# Discrete-Buck.net
KiCad netlist of a schematic drawn in EasyEDA Pro
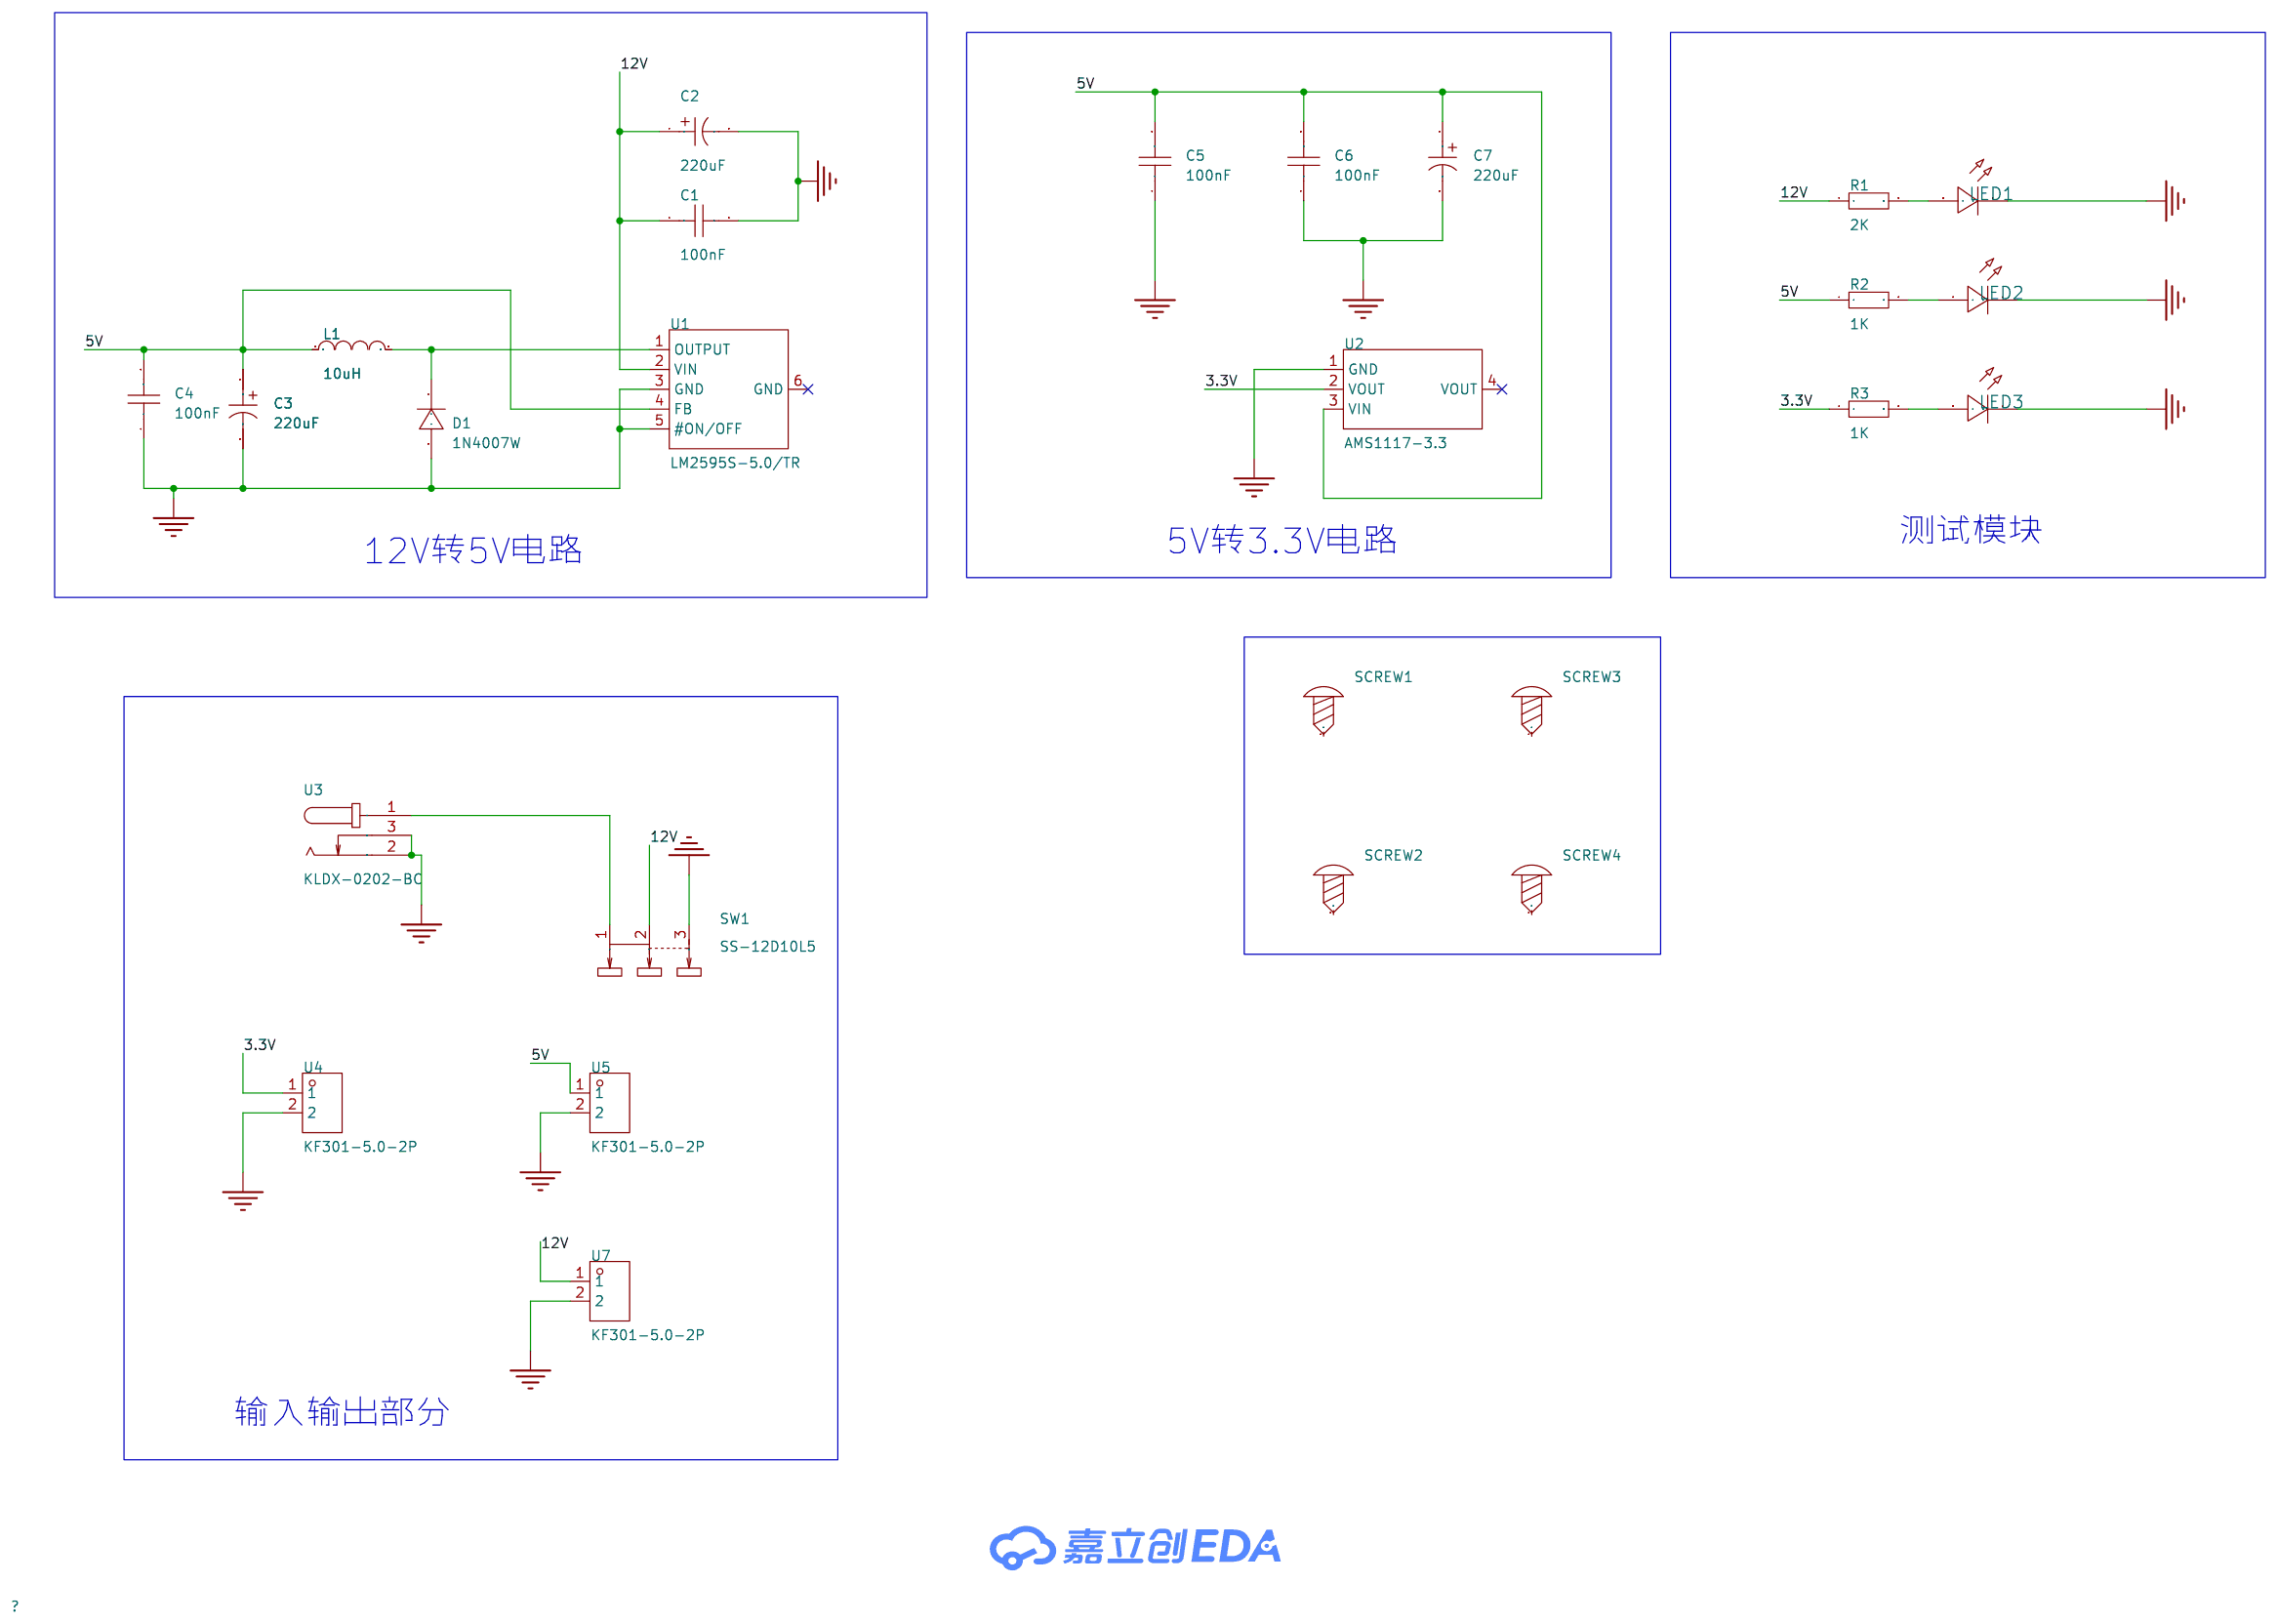
[diagram p0: schematic sheet]

(export (version "E")
  (design (tool "Eeschema 10.0.6"))
  (components
    (comp (ref "C1")
      (value "100nF")
      (footprint "easyedapro:C0603")
      (libsource (lib "easyedapro") (part "Capacitance"))
    )
    (comp (ref "C2")
      (value "220uF")
      (footprint "easyedapro:CAP-TH_BD6.3-P2.50-D0.5-FD")
      (description "容值:220uF;精度:±20%;额定电压:16V;纹波电流:300mA@100kHz;等效串联电阻(ESR):220mΩ@100kHz;")
      (fields (field (name "Manufacturer Part") "ERG16V220M6X7") (field (name "Manufacturer") "JIERR(捷而瑞)"))
      (libsource (lib "easyedapro") (part "ERG16V220M6X7"))
    )
    (comp (ref "C3")
      (value "220uF")
      (footprint "easyedapro:CAP-TH_BD6.3-P2.50-D0.5-FD")
      (description "容值:220uF;精度:±20%;额定电压:16V;纹波电流:300mA@100kHz;等效串联电阻(ESR):220mΩ@100kHz;")
      (fields (field (name "Manufacturer Part") "ERG16V220M6X7") (field (name "Manufacturer") "JIERR(捷而瑞)"))
      (libsource (lib "easyedapro") (part "ERG16V220M6X7"))
    )
    (comp (ref "C4")
      (value "100nF")
      (footprint "easyedapro:C0603")
      (libsource (lib "easyedapro") (part "Capacitance"))
    )
    (comp (ref "C5")
      (value "100nF")
      (footprint "easyedapro:C0603")
      (libsource (lib "easyedapro") (part "Capacitance"))
    )
    (comp (ref "C6")
      (value "100nF")
      (footprint "easyedapro:C0603")
      (libsource (lib "easyedapro") (part "Capacitance"))
    )
    (comp (ref "C7")
      (value "220uF")
      (footprint "easyedapro:CAP-TH_BD6.3-P2.50-D0.5-FD")
      (description "容值:220uF;精度:±20%;额定电压:16V;纹波电流:300mA@100kHz;等效串联电阻(ESR):220mΩ@100kHz;")
      (fields (field (name "Manufacturer Part") "ERG16V220M6X7") (field (name "Manufacturer") "JIERR(捷而瑞)"))
      (libsource (lib "easyedapro") (part "ERG16V220M6X7"))
    )
    (comp (ref "D1")
      (value "1N4007W")
      (footprint "easyedapro:SOD-123FL_L2.7-W1.8-LS3.8-RD")
      (description "二极管配置:独立式;正向压降(Vf):1V@1.0A;直流反向耐压(Vr):1kV;整流电流:1A;")
      (fields (field (name "Manufacturer") "R+O(宏嘉诚)"))
      (libsource (lib "easyedapro") (part "1N4007W_C18199088"))
    )
    (comp (ref "L1")
      (value "10uH")
      (footprint "easyedapro:L0603")
      (libsource (lib "easyedapro") (part "SDFL1608S100KTF"))
    )
    (comp (ref "LED1")
      (value "~")
      (footprint "easyedapro:LED_0603")
      (libsource (lib "easyedapro") (part "LED_R"))
    )
    (comp (ref "LED2")
      (value "~")
      (footprint "easyedapro:LED_0603")
      (libsource (lib "easyedapro") (part "LED_R"))
    )
    (comp (ref "LED3")
      (value "~")
      (footprint "easyedapro:LED_0603")
      (libsource (lib "easyedapro") (part "LED_R"))
    )
    (comp (ref "R1") (value "2K") (footprint "easyedapro:R0603") (libsource (lib "easyedapro") (part "电阻")))
    (comp (ref "R2") (value "1K") (footprint "easyedapro:R0603") (libsource (lib "easyedapro") (part "电阻")))
    (comp (ref "R3") (value "1K") (footprint "easyedapro:R0603") (libsource (lib "easyedapro") (part "电阻")))
    (comp (ref "SCREW1")
      (value "~")
      (footprint "easyedapro:M2螺丝")
      (libsource (lib "easyedapro") (part "螺丝孔"))
    )
    (comp (ref "SCREW2")
      (value "~")
      (footprint "easyedapro:M2螺丝")
      (libsource (lib "easyedapro") (part "螺丝孔"))
    )
    (comp (ref "SCREW3")
      (value "~")
      (footprint "easyedapro:M2螺丝")
      (libsource (lib "easyedapro") (part "螺丝孔"))
    )
    (comp (ref "SCREW4")
      (value "~")
      (footprint "easyedapro:M2螺丝")
      (libsource (lib "easyedapro") (part "螺丝孔"))
    )
    (comp (ref "SW1")
      (value "SS-12D10L5")
      (footprint "easyedapro:SW-TH_SS-12D10L5")
      (description "电路结构:单刀双掷;安装方式:直插;开关颜色:黑色;额定电流:3A;额定电压:125V;工作寿命:1万次;")
      (fields (field (name "Manufacturer") "XKB Connection(中国星坤)"))
      (libsource (lib "easyedapro") (part "SS-12D10L5"))
    )
    (comp (ref "U1")
      (value "LM2595S-5.0/TR")
      (footprint "easyedapro:TO-263-5_L10.6-W9.6-P1.70-LS15.9-BR")
      (description "功能类型:降压型;输出类型:固定;工作电压:4.5V~40V;输出电压:5V;输出电流:3A;")
      (fields (field (name "Manufacturer") "HGSEMI(华冠)"))
      (libsource (lib "easyedapro") (part "LM2595S-5.0/TR"))
    )
    (comp (ref "U2")
      (value "AMS1117-3.3")
      (footprint "easyedapro:SOT-223-3_L6.5-W3.4-P2.30-LS7.0-BR")
      (description "输出类型:固定;工作电压:16V;输出电压:3.3V;输出电流:1A;电源纹波抑制比(PSRR):72dB@(120Hz);输出极性:正极;")
      (fields (field (name "Manufacturer") "AMS"))
      (libsource (lib "easyedapro") (part "AMS1117-3.3"))
    )
    (comp (ref "U3")
      (value "KLDX-0202-BC")
      (footprint "easyedapro:DC-IN-TH_KH-DC-005-2.5")
      (fields (field (name "Manufacturer") "Kycon"))
      (libsource (lib "easyedapro") (part "KLDX-0202-BC"))
    )
    (comp (ref "U4")
      (value "KF301-5.0-2P")
      (footprint "easyedapro:CONN-TH_P5.00_KF301-5.0-2P")
      (fields (field (name "Manufacturer") "KEFA(科发)"))
      (libsource (lib "easyedapro") (part "KF301-5.0-2P"))
    )
    (comp (ref "U5")
      (value "KF301-5.0-2P")
      (footprint "easyedapro:CONN-TH_P5.00_KF301-5.0-2P")
      (fields (field (name "Manufacturer") "KEFA(科发)"))
      (libsource (lib "easyedapro") (part "KF301-5.0-2P"))
    )
    (comp (ref "U7")
      (value "KF301-5.0-2P")
      (footprint "easyedapro:CONN-TH_P5.00_KF301-5.0-2P")
      (fields (field (name "Manufacturer") "KEFA(科发)"))
      (libsource (lib "easyedapro") (part "KF301-5.0-2P"))
    )
  )
  (nets
    (net (code "1") (name "/3.3V") (class "Default")
      (node (ref "R3") (pin "1") (pinfunction "1_1") (pintype "input"))
      (node (ref "U2") (pin "2") (pinfunction "VOUT_2") (pintype "unspecified"))
      (node (ref "U4") (pin "1") (pinfunction "1_1") (pintype "unspecified"))
    )
    (net (code "2") (name "/5V") (class "Default")
      (node (ref "C3") (pin "1") (pinfunction "1_1") (pintype "input"))
      (node (ref "C4") (pin "2") (pinfunction "2_2") (pintype "input"))
      (node (ref "C5") (pin "2") (pinfunction "2_2") (pintype "input"))
      (node (ref "C6") (pin "2") (pinfunction "2_2") (pintype "input"))
      (node (ref "C7") (pin "1") (pinfunction "1_1") (pintype "input"))
      (node (ref "L1") (pin "1") (pinfunction "1_1") (pintype "unspecified"))
      (node (ref "R2") (pin "1") (pinfunction "1_1") (pintype "input"))
      (node (ref "U1") (pin "4") (pinfunction "FB_4") (pintype "unspecified"))
      (node (ref "U2") (pin "3") (pinfunction "VIN_3") (pintype "unspecified"))
      (node (ref "U5") (pin "1") (pinfunction "1_1") (pintype "unspecified"))
    )
    (net (code "3") (name "/12V") (class "Default")
      (node (ref "C1") (pin "1") (pinfunction "1_1") (pintype "input"))
      (node (ref "C2") (pin "1") (pinfunction "1_1") (pintype "input"))
      (node (ref "R1") (pin "1") (pinfunction "1_1") (pintype "input"))
      (node (ref "SW1") (pin "2") (pinfunction "2_2") (pintype "unspecified"))
      (node (ref "U1") (pin "2") (pinfunction "VIN_2") (pintype "unspecified"))
      (node (ref "U7") (pin "1") (pinfunction "1_1") (pintype "unspecified"))
    )
    (net (code "4") (name "GND") (class "Default")
      (node (ref "C1") (pin "2") (pinfunction "2_2") (pintype "input"))
      (node (ref "C2") (pin "2") (pinfunction "2_2") (pintype "input"))
      (node (ref "C3") (pin "2") (pinfunction "2_2") (pintype "input"))
      (node (ref "C4") (pin "1") (pinfunction "1_1") (pintype "input"))
      (node (ref "C5") (pin "1") (pinfunction "1_1") (pintype "input"))
      (node (ref "C6") (pin "1") (pinfunction "1_1") (pintype "input"))
      (node (ref "C7") (pin "2") (pinfunction "2_2") (pintype "input"))
      (node (ref "D1") (pin "2") (pinfunction "A_2") (pintype "unspecified"))
      (node (ref "LED1") (pin "1") (pinfunction "C_1") (pintype "input"))
      (node (ref "LED2") (pin "1") (pinfunction "C_1") (pintype "input"))
      (node (ref "LED3") (pin "1") (pinfunction "C_1") (pintype "input"))
      (node (ref "SW1") (pin "3") (pinfunction "3_3") (pintype "unspecified"))
      (node (ref "U1") (pin "3") (pinfunction "GND_3") (pintype "unspecified"))
      (node (ref "U1") (pin "5") (pinfunction "#ON/OFF_5") (pintype "unspecified"))
      (node (ref "U2") (pin "1") (pinfunction "GND_1") (pintype "unspecified"))
      (node (ref "U3") (pin "2") (pinfunction "2_2") (pintype "unspecified"))
      (node (ref "U3") (pin "3") (pinfunction "3_3") (pintype "unspecified"))
      (node (ref "U4") (pin "2") (pinfunction "2_2") (pintype "unspecified"))
      (node (ref "U5") (pin "2") (pinfunction "2_2") (pintype "unspecified"))
      (node (ref "U7") (pin "2") (pinfunction "2_2") (pintype "unspecified"))
    )
    (net (code "5") (name "Net-(D1-K)") (class "Default")
      (node (ref "D1") (pin "1") (pinfunction "K_1") (pintype "unspecified"))
      (node (ref "L1") (pin "2") (pinfunction "2_2") (pintype "unspecified"))
      (node (ref "U1") (pin "1") (pinfunction "OUTPUT_1") (pintype "unspecified"))
    )
    (net (code "6") (name "Net-(LED1-A)") (class "Default")
      (node (ref "LED1") (pin "2") (pinfunction "A_2") (pintype "input"))
      (node (ref "R1") (pin "2") (pinfunction "2_2") (pintype "input"))
    )
    (net (code "7") (name "Net-(LED2-A)") (class "Default")
      (node (ref "LED2") (pin "2") (pinfunction "A_2") (pintype "input"))
      (node (ref "R2") (pin "2") (pinfunction "2_2") (pintype "input"))
    )
    (net (code "8") (name "Net-(LED3-A)") (class "Default")
      (node (ref "LED3") (pin "2") (pinfunction "A_2") (pintype "input"))
      (node (ref "R3") (pin "2") (pinfunction "2_2") (pintype "input"))
    )
    (net (code "9") (name "Net-(SW1-Pad1)") (class "Default")
      (node (ref "SW1") (pin "1") (pinfunction "1_1") (pintype "unspecified"))
      (node (ref "U3") (pin "1") (pinfunction "1_1") (pintype "unspecified"))
    )
    (net (code "10") (name "unconnected-(SCREW1-Pad1)") (class "Default")
      (node (ref "SCREW1") (pin "1") (pinfunction "1_1") (pintype "input"))
    )
    (net (code "11") (name "unconnected-(SCREW2-Pad1)") (class "Default")
      (node (ref "SCREW2") (pin "1") (pinfunction "1_1") (pintype "input"))
    )
    (net (code "12") (name "unconnected-(SCREW3-Pad1)") (class "Default")
      (node (ref "SCREW3") (pin "1") (pinfunction "1_1") (pintype "input"))
    )
    (net (code "13") (name "unconnected-(SCREW4-Pad1)") (class "Default")
      (node (ref "SCREW4") (pin "1") (pinfunction "1_1") (pintype "input"))
    )
    (net (code "14") (name "unconnected-(U1-GND-Pad6)") (class "Default")
      (node (ref "U1") (pin "6") (pinfunction "GND_6") (pintype "unspecified+no_connect"))
    )
    (net (code "15") (name "unconnected-(U2-VOUT-Pad4)") (class "Default")
      (node (ref "U2") (pin "4") (pinfunction "VOUT_4") (pintype "unspecified+no_connect"))
    )
  )
)
